# link.net
KiCad netlist of a schematic drawn in EAGLE
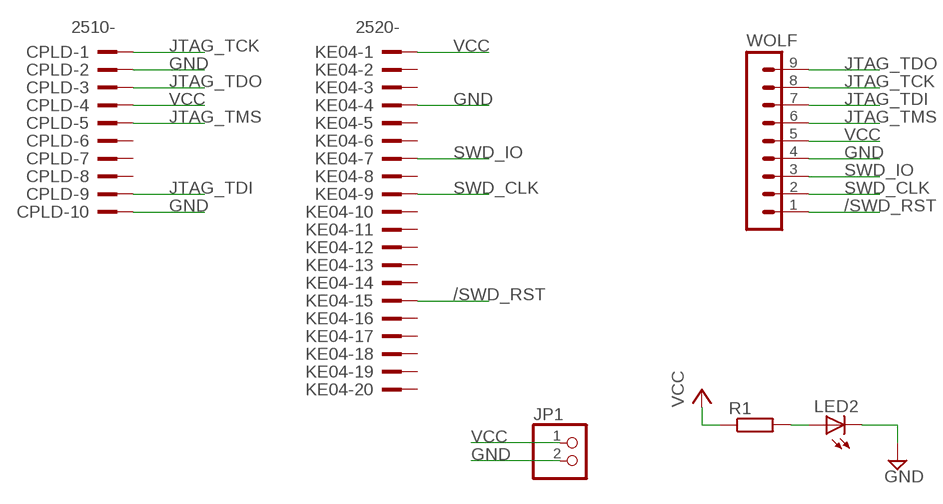
[diagram p0: schematic, sheet 1]

(export (version "E")
  (design (tool "Eeschema 10.0.6"))
  (components
    (comp (ref "CPLD")
      (value "2510-")
      (footprint "eagle-import:PAK100_2500-10")
      (fields (field (name "MF") "3M") (field (name "MPN") "2510-6002UB"))
      (libsource (lib "eagle-import") (part "2510-"))
    )
    (comp (ref "JP1")
      (value "PINHD-1X2")
      (footprint "eagle-import:1X02")
      (libsource (lib "eagle-import") (part "PINHD-1X2"))
    )
    (comp (ref "KE04")
      (value "2520-")
      (footprint "eagle-import:PAK100_2500-20")
      (libsource (lib "eagle-import") (part "2520-"))
    )
    (comp (ref "LED2")
      (value "LEDSML0805")
      (footprint "eagle-import:SML0805")
      (libsource (lib "eagle-import") (part "LEDSML0805"))
    )
    (comp (ref "R1")
      (value "R-EU_R0805")
      (footprint "eagle-import:R0805")
      (libsource (lib "eagle-import") (part "R-EU_R0805"))
    )
    (comp (ref "WOLF")
      (value "MA09-1")
      (footprint "eagle-import:MA09-1")
      (libsource (lib "eagle-import") (part "MA09-1"))
    )
  )
  (nets
    (net (code "1") (name "/JTAG_TCK") (class "Default")
      (node (ref "CPLD") (pin "1") (pinfunction "KL_1") (pintype "passive"))
      (node (ref "WOLF") (pin "8") (pinfunction "8_8") (pintype "passive"))
    )
    (net (code "2") (name "/JTAG_TDI") (class "Default")
      (node (ref "CPLD") (pin "9") (pinfunction "KL_9") (pintype "passive"))
      (node (ref "WOLF") (pin "7") (pinfunction "7_7") (pintype "passive"))
    )
    (net (code "3") (name "/JTAG_TDO") (class "Default")
      (node (ref "CPLD") (pin "3") (pinfunction "KL_3") (pintype "passive"))
      (node (ref "WOLF") (pin "9") (pinfunction "9_9") (pintype "passive"))
    )
    (net (code "4") (name "/JTAG_TMS") (class "Default")
      (node (ref "CPLD") (pin "5") (pinfunction "KL_5") (pintype "passive"))
      (node (ref "WOLF") (pin "6") (pinfunction "6_6") (pintype "passive"))
    )
    (net (code "5") (name "/SWD_CLK") (class "Default")
      (node (ref "KE04") (pin "9") (pinfunction "KL_9") (pintype "passive"))
      (node (ref "WOLF") (pin "2") (pinfunction "2_2") (pintype "passive"))
    )
    (net (code "6") (name "/SWD_IO") (class "Default")
      (node (ref "KE04") (pin "7") (pinfunction "KL_7") (pintype "passive"))
      (node (ref "WOLF") (pin "3") (pinfunction "3_3") (pintype "passive"))
    )
    (net (code "7") (name "/{slash}SWD_RST") (class "Default")
      (node (ref "KE04") (pin "15") (pinfunction "KL_15") (pintype "passive"))
      (node (ref "WOLF") (pin "1") (pinfunction "1_1") (pintype "passive"))
    )
    (net (code "8") (name "GND") (class "Default")
      (node (ref "CPLD") (pin "10") (pinfunction "KL_10") (pintype "passive"))
      (node (ref "CPLD") (pin "2") (pinfunction "KL_2") (pintype "passive"))
      (node (ref "JP1") (pin "2") (pinfunction "2_2") (pintype "passive"))
      (node (ref "KE04") (pin "4") (pinfunction "KL_4") (pintype "passive"))
      (node (ref "LED2") (pin "C") (pinfunction "C_C") (pintype "passive"))
      (node (ref "WOLF") (pin "4") (pinfunction "4_4") (pintype "passive"))
    )
    (net (code "9") (name "Net-(LED2-PadA)") (class "Default")
      (node (ref "LED2") (pin "A") (pinfunction "A_A") (pintype "passive"))
      (node (ref "R1") (pin "2") (pinfunction "2_2") (pintype "passive"))
    )
    (net (code "10") (name "VCC") (class "Default")
      (node (ref "CPLD") (pin "4") (pinfunction "KL_4") (pintype "passive"))
      (node (ref "JP1") (pin "1") (pinfunction "1_1") (pintype "passive"))
      (node (ref "KE04") (pin "1") (pinfunction "KL_1") (pintype "passive"))
      (node (ref "R1") (pin "1") (pinfunction "1_1") (pintype "passive"))
      (node (ref "WOLF") (pin "5") (pinfunction "5_5") (pintype "passive"))
    )
    (net (code "11") (name "unconnected-(CPLDG-KL-Pad6)") (class "Default")
      (node (ref "CPLD") (pin "6") (pinfunction "KL_6") (pintype "passive"))
    )
    (net (code "12") (name "unconnected-(CPLDH-KL-Pad7)") (class "Default")
      (node (ref "CPLD") (pin "7") (pinfunction "KL_7") (pintype "passive"))
    )
    (net (code "13") (name "unconnected-(CPLDI-KL-Pad8)") (class "Default")
      (node (ref "CPLD") (pin "8") (pinfunction "KL_8") (pintype "passive"))
    )
    (net (code "14") (name "unconnected-(KE04B-KL-Pad10)") (class "Default")
      (node (ref "KE04") (pin "10") (pinfunction "KL_10") (pintype "passive"))
    )
    (net (code "15") (name "unconnected-(KE04C-KL-Pad11)") (class "Default")
      (node (ref "KE04") (pin "11") (pinfunction "KL_11") (pintype "passive"))
    )
    (net (code "16") (name "unconnected-(KE04D-KL-Pad12)") (class "Default")
      (node (ref "KE04") (pin "12") (pinfunction "KL_12") (pintype "passive"))
    )
    (net (code "17") (name "unconnected-(KE04E-KL-Pad13)") (class "Default")
      (node (ref "KE04") (pin "13") (pinfunction "KL_13") (pintype "passive"))
    )
    (net (code "18") (name "unconnected-(KE04F-KL-Pad14)") (class "Default")
      (node (ref "KE04") (pin "14") (pinfunction "KL_14") (pintype "passive"))
    )
    (net (code "19") (name "unconnected-(KE04H-KL-Pad16)") (class "Default")
      (node (ref "KE04") (pin "16") (pinfunction "KL_16") (pintype "passive"))
    )
    (net (code "20") (name "unconnected-(KE04I-KL-Pad17)") (class "Default")
      (node (ref "KE04") (pin "17") (pinfunction "KL_17") (pintype "passive"))
    )
    (net (code "21") (name "unconnected-(KE04J-KL-Pad18)") (class "Default")
      (node (ref "KE04") (pin "18") (pinfunction "KL_18") (pintype "passive"))
    )
    (net (code "22") (name "unconnected-(KE04K-KL-Pad19)") (class "Default")
      (node (ref "KE04") (pin "19") (pinfunction "KL_19") (pintype "passive"))
    )
    (net (code "23") (name "unconnected-(KE04L-KL-Pad2)") (class "Default")
      (node (ref "KE04") (pin "2") (pinfunction "KL_2") (pintype "passive"))
    )
    (net (code "24") (name "unconnected-(KE04M-KL-Pad20)") (class "Default")
      (node (ref "KE04") (pin "20") (pinfunction "KL_20") (pintype "passive"))
    )
    (net (code "25") (name "unconnected-(KE04N-KL-Pad3)") (class "Default")
      (node (ref "KE04") (pin "3") (pinfunction "KL_3") (pintype "passive"))
    )
    (net (code "26") (name "unconnected-(KE04P-KL-Pad5)") (class "Default")
      (node (ref "KE04") (pin "5") (pinfunction "KL_5") (pintype "passive"))
    )
    (net (code "27") (name "unconnected-(KE04Q-KL-Pad6)") (class "Default")
      (node (ref "KE04") (pin "6") (pinfunction "KL_6") (pintype "passive"))
    )
    (net (code "28") (name "unconnected-(KE04S-KL-Pad8)") (class "Default")
      (node (ref "KE04") (pin "8") (pinfunction "KL_8") (pintype "passive"))
    )
  )
)
